# ERG-2025-2.net
KiCad netlist of a schematic drawn in EasyEDA Pro
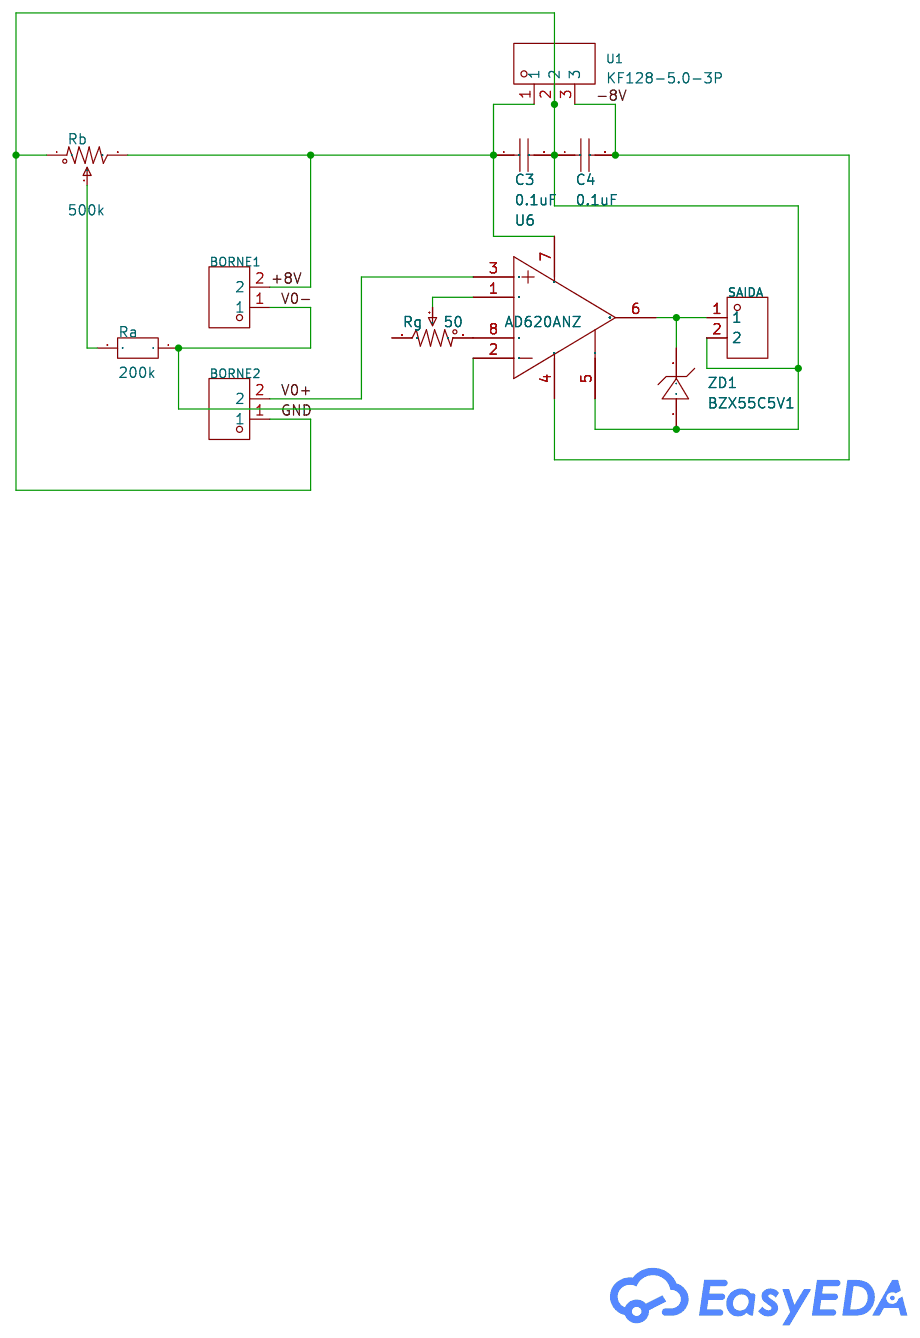
[diagram p0: schematic sheet]

(export (version "E")
  (design (tool "Eeschema 10.0.6"))
  (components
    (comp (ref "BORNE1")
      (value "KF128L-5.08-2P")
      (footprint "easyedapro:CONN-TH_P5.08_KF128L-5.08-2P")
      (fields (field (name "Manufacturer") "KEFA(科发)"))
      (libsource (lib "easyedapro") (part "KF128L-5.08-2P"))
    )
    (comp (ref "BORNE2")
      (value "KF128L-5.08-2P")
      (footprint "easyedapro:CONN-TH_P5.08_KF128L-5.08-2P")
      (fields (field (name "Manufacturer") "KEFA(科发)"))
      (libsource (lib "easyedapro") (part "KF128L-5.08-2P"))
    )
    (comp (ref "C3")
      (value "0.1uF")
      (footprint "easyedapro:CAP-TH_L8.5-W5.0-P5.00-D1.2")
      (description "Capacitance:1uF Tolerance:±10% Tolerance:±10% Voltage Rating:50V Temperature Coefficient:X7R")
      (fields (field (name "Manufacturer Part") "CT4-0805B105K500F3") (field (name "Manufacturer") "FH(风华)"))
      (libsource (lib "easyedapro") (part "CT4-0805B105K500F3"))
    )
    (comp (ref "C4")
      (value "0.1uF")
      (footprint "easyedapro:CAP-TH_L8.5-W5.0-P5.00-D1.2")
      (description "Capacitance:1uF Tolerance:±10% Tolerance:±10% Voltage Rating:50V Temperature Coefficient:X7R")
      (fields (field (name "Manufacturer Part") "CT4-0805B105K500F3") (field (name "Manufacturer") "FH(风华)"))
      (libsource (lib "easyedapro") (part "CT4-0805B105K500F3"))
    )
    (comp (ref "Ra")
      (value "200k")
      (footprint "easyedapro:RES-TH_BD2.3-L6.5-P10.50-D0.5")
      (fields (field (name "Manufacturer Part") "MF1/4W-1KΩ±1%T52") (field (name "Manufacturer") "华星机电"))
      (libsource (lib "easyedapro") (part "MF1/4W-1KΩ±1%T52"))
    )
    (comp (ref "Rb")
      (value "500k")
      (footprint "easyedapro:RES-ADJ-TH_3P-L10.0-W10.0-P2.50-L")
      (description "Resistance: Tolerance:±10% Tolerance:±10%")
      (fields (field (name "Manufacturer Part") "3296W-1-103") (field (name "Manufacturer") "BOCHEN(博晨)"))
      (libsource (lib "easyedapro") (part "3296W-1-103"))
    )
    (comp (ref "Rg")
      (value "50")
      (footprint "easyedapro:RES-ADJ-TH_3P-L10.0-W10.0-P2.50-L")
      (description "Resistance: Tolerance:±10% Tolerance:±10%")
      (fields (field (name "Manufacturer Part") "3296W-1-103") (field (name "Manufacturer") "BOCHEN(博晨)"))
      (libsource (lib "easyedapro") (part "3296W-1-103"))
    )
    (comp (ref "SAIDA")
      (value "KF128L-5.08-2P")
      (footprint "easyedapro:CONN-TH_P5.08_KF128L-5.08-2P")
      (fields (field (name "Manufacturer") "KEFA(科发)"))
      (libsource (lib "easyedapro") (part "KF128L-5.08-2P"))
    )
    (comp (ref "U1")
      (value "KF128-5.0-3P")
      (footprint "easyedapro:CONN-TH_3P-P5.00_KF128-5.0-3P")
      (fields (field (name "Manufacturer") "KEFA(科发)"))
      (libsource (lib "easyedapro") (part "KF128-5.0-3P"))
    )
    (comp (ref "U6")
      (value "AD620ANZ")
      (footprint "easyedapro:DIP-8_L9.3-W6.4-P2.54-LS7.6-BL")
      (fields (field (name "Manufacturer") "ADI(亚德诺)"))
      (libsource (lib "easyedapro") (part "AD620ANZ"))
    )
    (comp (ref "ZD1")
      (value "BZX55C5V1")
      (footprint "easyedapro:DO-35_BD2.0-L4.0-P8.00-D0.5-FD")
      (fields (field (name "Manufacturer") "ST(先科)"))
      (libsource (lib "easyedapro") (part "BZX55C5V1"))
    )
  )
  (nets
    (net (code "1") (name "/+8V") (class "Default")
      (node (ref "BORNE1") (pin "2") (pinfunction "2_2") (pintype "input"))
      (node (ref "C3") (pin "1") (pinfunction "1_1") (pintype "input"))
      (node (ref "Rb") (pin "3") (pinfunction "3_3") (pintype "input"))
      (node (ref "U1") (pin "1") (pinfunction "1_1") (pintype "input"))
      (node (ref "U6") (pin "7") (pinfunction "+VS_7") (pintype "unspecified"))
    )
    (net (code "2") (name "/-8V") (class "Default")
      (node (ref "C4") (pin "2") (pinfunction "2_2") (pintype "input"))
      (node (ref "U1") (pin "3") (pinfunction "3_3") (pintype "input"))
      (node (ref "U6") (pin "4") (pinfunction "-VS_4") (pintype "unspecified"))
    )
    (net (code "3") (name "/GND") (class "Default")
      (node (ref "BORNE2") (pin "1") (pinfunction "1_1") (pintype "input"))
      (node (ref "C3") (pin "2") (pinfunction "2_2") (pintype "input"))
      (node (ref "C4") (pin "1") (pinfunction "1_1") (pintype "input"))
      (node (ref "Rb") (pin "1") (pinfunction "1_1") (pintype "input"))
      (node (ref "SAIDA") (pin "2") (pinfunction "2_2") (pintype "input"))
      (node (ref "U1") (pin "2") (pinfunction "2_2") (pintype "input"))
      (node (ref "U6") (pin "5") (pinfunction "REF_5") (pintype "input"))
      (node (ref "ZD1") (pin "1") (pinfunction "A_1") (pintype "unspecified"))
    )
    (net (code "4") (name "/V0+") (class "Default")
      (node (ref "BORNE2") (pin "2") (pinfunction "2_2") (pintype "input"))
      (node (ref "U6") (pin "3") (pinfunction "+IN_3") (pintype "input"))
    )
    (net (code "5") (name "/V0-") (class "Default")
      (node (ref "BORNE1") (pin "1") (pinfunction "1_1") (pintype "input"))
      (node (ref "Ra") (pin "1") (pinfunction "1_1") (pintype "unspecified"))
      (node (ref "U6") (pin "2") (pinfunction "-IN_2") (pintype "input"))
    )
    (net (code "6") (name "Net-(Ra-Pad2)") (class "Default")
      (node (ref "Ra") (pin "2") (pinfunction "2_2") (pintype "unspecified"))
      (node (ref "Rb") (pin "2") (pinfunction "2_2") (pintype "input"))
    )
    (net (code "7") (name "Net-(Rg-Pad1)") (class "Default")
      (node (ref "Rg") (pin "1") (pinfunction "1_1") (pintype "input"))
      (node (ref "U6") (pin "8") (pinfunction "RG_8") (pintype "unspecified"))
    )
    (net (code "8") (name "Net-(Rg-Pad2)") (class "Default")
      (node (ref "Rg") (pin "2") (pinfunction "2_2") (pintype "input"))
      (node (ref "U6") (pin "1") (pinfunction "RG_1") (pintype "unspecified"))
    )
    (net (code "9") (name "Net-(U6-OUTPUT)") (class "Default")
      (node (ref "SAIDA") (pin "1") (pinfunction "1_1") (pintype "input"))
      (node (ref "U6") (pin "6") (pinfunction "OUTPUT_6") (pintype "output"))
      (node (ref "ZD1") (pin "2") (pinfunction "K_2") (pintype "unspecified"))
    )
    (net (code "10") (name "unconnected-(Rg-Pad3)") (class "Default")
      (node (ref "Rg") (pin "3") (pinfunction "3_3") (pintype "input"))
    )
  )
)
